# mael.net
KiCad netlist of a schematic drawn in EAGLE
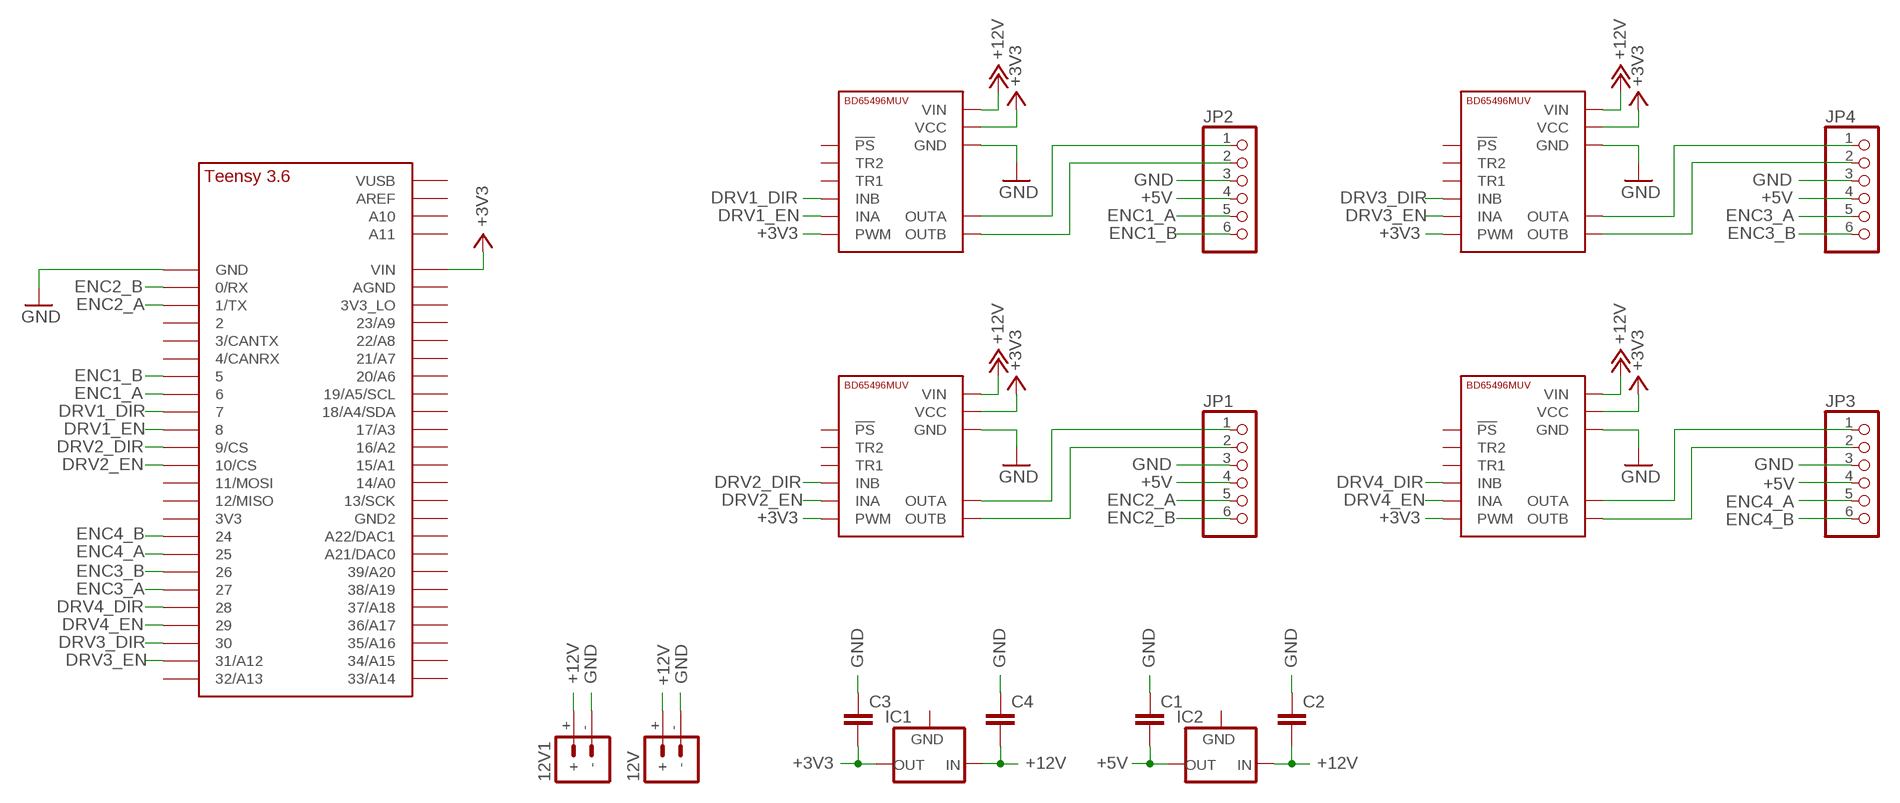
[diagram p0: schematic, sheet 1]

(export (version "E")
  (design (tool "Eeschema 10.0.6"))
  (components
    (comp (ref "12V")
      (value "BATTERY_CONN_DEANS")
      (footprint "eagle-import:DEANS")
      (libsource (lib "eagle-import") (part "BATTERY_CONN_DEANS"))
    )
    (comp (ref "12V1")
      (value "BATTERY_CONN_DEANS")
      (footprint "eagle-import:DEANS")
      (libsource (lib "eagle-import") (part "BATTERY_CONN_DEANS"))
    )
    (comp (ref "C1")
      (value "C-EU050-024X044")
      (footprint "eagle-import:C050-024X044")
      (libsource (lib "eagle-import") (part "C-EU050-024X044"))
    )
    (comp (ref "C2")
      (value "C-EU050-024X044")
      (footprint "eagle-import:C050-024X044")
      (libsource (lib "eagle-import") (part "C-EU050-024X044"))
    )
    (comp (ref "C3")
      (value "C-EU050-024X044")
      (footprint "eagle-import:C050-024X044")
      (libsource (lib "eagle-import") (part "C-EU050-024X044"))
    )
    (comp (ref "C4")
      (value "C-EU050-024X044")
      (footprint "eagle-import:C050-024X044")
      (libsource (lib "eagle-import") (part "C-EU050-024X044"))
    )
    (comp (ref "IC1")
      (value "78XXL")
      (footprint "eagle-import:78XXL")
      (libsource (lib "eagle-import") (part "78XXL"))
    )
    (comp (ref "IC2")
      (value "78XXL")
      (footprint "eagle-import:78XXL")
      (libsource (lib "eagle-import") (part "78XXL"))
    )
    (comp (ref "JP1")
      (value "PINHD-1X6")
      (footprint "eagle-import:1X06")
      (libsource (lib "eagle-import") (part "PINHD-1X6"))
    )
    (comp (ref "JP2")
      (value "PINHD-1X6")
      (footprint "eagle-import:1X06")
      (libsource (lib "eagle-import") (part "PINHD-1X6"))
    )
    (comp (ref "JP3")
      (value "PINHD-1X6")
      (footprint "eagle-import:1X06")
      (libsource (lib "eagle-import") (part "PINHD-1X6"))
    )
    (comp (ref "JP4")
      (value "PINHD-1X6")
      (footprint "eagle-import:1X06")
      (libsource (lib "eagle-import") (part "PINHD-1X6"))
    )
    (comp (ref "U$1")
      (value "BD65496MUV")
      (footprint "eagle-import:BD65496MUV")
      (libsource (lib "eagle-import") (part "BD65496MUV"))
    )
    (comp (ref "U$2")
      (value "TEENSY_3.5/3.6_BASIC")
      (footprint "eagle-import:TEENSY_3.5_3.6_BASIC")
      (libsource (lib "eagle-import") (part "TEENSY_3.5/3.6_BASIC"))
    )
    (comp (ref "U$3")
      (value "BD65496MUV")
      (footprint "eagle-import:BD65496MUV")
      (libsource (lib "eagle-import") (part "BD65496MUV"))
    )
    (comp (ref "U$4")
      (value "BD65496MUV")
      (footprint "eagle-import:BD65496MUV")
      (libsource (lib "eagle-import") (part "BD65496MUV"))
    )
    (comp (ref "U$5")
      (value "BD65496MUV")
      (footprint "eagle-import:BD65496MUV")
      (libsource (lib "eagle-import") (part "BD65496MUV"))
    )
  )
  (nets
    (net (code "1") (name "+3V3") (class "Default")
      (node (ref "C3") (pin "2") (pinfunction "2_2") (pintype "passive"))
      (node (ref "IC1") (pin "OUT") (pinfunction "OUT_OUT") (pintype "passive"))
      (node (ref "U$1") (pin "PWM") (pinfunction "PWM_PWM") (pintype "bidirectional"))
      (node (ref "U$1") (pin "VCC") (pinfunction "VCC_VCC") (pintype "bidirectional"))
      (node (ref "U$2") (pin "VIN") (pinfunction "VIN_VIN") (pintype "bidirectional"))
      (node (ref "U$3") (pin "PWM") (pinfunction "PWM_PWM") (pintype "bidirectional"))
      (node (ref "U$3") (pin "VCC") (pinfunction "VCC_VCC") (pintype "bidirectional"))
      (node (ref "U$4") (pin "PWM") (pinfunction "PWM_PWM") (pintype "bidirectional"))
      (node (ref "U$4") (pin "VCC") (pinfunction "VCC_VCC") (pintype "bidirectional"))
      (node (ref "U$5") (pin "PWM") (pinfunction "PWM_PWM") (pintype "bidirectional"))
      (node (ref "U$5") (pin "VCC") (pinfunction "VCC_VCC") (pintype "bidirectional"))
    )
    (net (code "2") (name "+12V") (class "Default")
      (node (ref "12V") (pin "+") (pinfunction "+_+") (pintype "passive"))
      (node (ref "12V1") (pin "+") (pinfunction "+_+") (pintype "passive"))
      (node (ref "C2") (pin "2") (pinfunction "2_2") (pintype "passive"))
      (node (ref "C4") (pin "2") (pinfunction "2_2") (pintype "passive"))
      (node (ref "IC1") (pin "IN") (pinfunction "IN_IN") (pintype "input"))
      (node (ref "IC2") (pin "IN") (pinfunction "IN_IN") (pintype "input"))
      (node (ref "U$1") (pin "VIN") (pinfunction "VIN_VIN") (pintype "bidirectional"))
      (node (ref "U$3") (pin "VIN") (pinfunction "VIN_VIN") (pintype "bidirectional"))
      (node (ref "U$4") (pin "VIN") (pinfunction "VIN_VIN") (pintype "bidirectional"))
      (node (ref "U$5") (pin "VIN") (pinfunction "VIN_VIN") (pintype "bidirectional"))
    )
    (net (code "3") (name "/+5V") (class "Default")
      (node (ref "C1") (pin "2") (pinfunction "2_2") (pintype "passive"))
      (node (ref "IC2") (pin "OUT") (pinfunction "OUT_OUT") (pintype "passive"))
      (node (ref "JP1") (pin "4") (pinfunction "4_4") (pintype "passive"))
      (node (ref "JP2") (pin "4") (pinfunction "4_4") (pintype "passive"))
      (node (ref "JP3") (pin "4") (pinfunction "4_4") (pintype "passive"))
      (node (ref "JP4") (pin "4") (pinfunction "4_4") (pintype "passive"))
    )
    (net (code "4") (name "/DRV1_DIR") (class "Default")
      (node (ref "U$1") (pin "INB") (pinfunction "INB_INB") (pintype "bidirectional"))
      (node (ref "U$2") (pin "7") (pinfunction "7_7") (pintype "bidirectional"))
    )
    (net (code "5") (name "/DRV1_EN") (class "Default")
      (node (ref "U$1") (pin "INA") (pinfunction "INA_INA") (pintype "bidirectional"))
      (node (ref "U$2") (pin "8") (pinfunction "8_8") (pintype "bidirectional"))
    )
    (net (code "6") (name "/DRV2_DIR") (class "Default")
      (node (ref "U$2") (pin "9/CS") (pinfunction "9/CS_9/CS") (pintype "bidirectional"))
      (node (ref "U$3") (pin "INB") (pinfunction "INB_INB") (pintype "bidirectional"))
    )
    (net (code "7") (name "/DRV2_EN") (class "Default")
      (node (ref "U$2") (pin "10/CS") (pinfunction "10/CS_10/CS") (pintype "bidirectional"))
      (node (ref "U$3") (pin "INA") (pinfunction "INA_INA") (pintype "bidirectional"))
    )
    (net (code "8") (name "/DRV3_DIR") (class "Default")
      (node (ref "U$2") (pin "30") (pinfunction "30_30") (pintype "bidirectional"))
      (node (ref "U$4") (pin "INB") (pinfunction "INB_INB") (pintype "bidirectional"))
    )
    (net (code "9") (name "/DRV3_EN") (class "Default")
      (node (ref "U$2") (pin "31/A12") (pinfunction "31/A12_31/A12") (pintype "bidirectional"))
      (node (ref "U$4") (pin "INA") (pinfunction "INA_INA") (pintype "bidirectional"))
    )
    (net (code "10") (name "/DRV4_DIR") (class "Default")
      (node (ref "U$2") (pin "28") (pinfunction "28_28") (pintype "bidirectional"))
      (node (ref "U$5") (pin "INB") (pinfunction "INB_INB") (pintype "bidirectional"))
    )
    (net (code "11") (name "/DRV4_EN") (class "Default")
      (node (ref "U$2") (pin "29") (pinfunction "29_29") (pintype "bidirectional"))
      (node (ref "U$5") (pin "INA") (pinfunction "INA_INA") (pintype "bidirectional"))
    )
    (net (code "12") (name "/ENC1_A") (class "Default")
      (node (ref "JP2") (pin "5") (pinfunction "5_5") (pintype "passive"))
      (node (ref "U$2") (pin "6") (pinfunction "6_6") (pintype "bidirectional"))
    )
    (net (code "13") (name "/ENC1_B") (class "Default")
      (node (ref "JP2") (pin "6") (pinfunction "6_6") (pintype "passive"))
      (node (ref "U$2") (pin "5") (pinfunction "5_5") (pintype "bidirectional"))
    )
    (net (code "14") (name "/ENC2_A") (class "Default")
      (node (ref "JP1") (pin "5") (pinfunction "5_5") (pintype "passive"))
      (node (ref "U$2") (pin "1/TX") (pinfunction "1/TX_1/TX") (pintype "bidirectional"))
    )
    (net (code "15") (name "/ENC2_B") (class "Default")
      (node (ref "JP1") (pin "6") (pinfunction "6_6") (pintype "passive"))
      (node (ref "U$2") (pin "0/RX") (pinfunction "0/RX_0/RX") (pintype "bidirectional"))
    )
    (net (code "16") (name "/ENC3_A") (class "Default")
      (node (ref "JP4") (pin "5") (pinfunction "5_5") (pintype "passive"))
      (node (ref "U$2") (pin "27") (pinfunction "27_27") (pintype "bidirectional"))
    )
    (net (code "17") (name "/ENC3_B") (class "Default")
      (node (ref "JP4") (pin "6") (pinfunction "6_6") (pintype "passive"))
      (node (ref "U$2") (pin "26") (pinfunction "26_26") (pintype "bidirectional"))
    )
    (net (code "18") (name "/ENC4_A") (class "Default")
      (node (ref "JP3") (pin "5") (pinfunction "5_5") (pintype "passive"))
      (node (ref "U$2") (pin "25") (pinfunction "25_25") (pintype "bidirectional"))
    )
    (net (code "19") (name "/ENC4_B") (class "Default")
      (node (ref "JP3") (pin "6") (pinfunction "6_6") (pintype "passive"))
      (node (ref "U$2") (pin "24") (pinfunction "24_24") (pintype "bidirectional"))
    )
    (net (code "20") (name "GND") (class "Default")
      (node (ref "12V") (pin "-") (pinfunction "-_-") (pintype "passive"))
      (node (ref "12V1") (pin "-") (pinfunction "-_-") (pintype "passive"))
      (node (ref "C1") (pin "1") (pinfunction "1_1") (pintype "passive"))
      (node (ref "C2") (pin "1") (pinfunction "1_1") (pintype "passive"))
      (node (ref "C3") (pin "1") (pinfunction "1_1") (pintype "passive"))
      (node (ref "C4") (pin "1") (pinfunction "1_1") (pintype "passive"))
      (node (ref "JP1") (pin "3") (pinfunction "3_3") (pintype "passive"))
      (node (ref "JP2") (pin "3") (pinfunction "3_3") (pintype "passive"))
      (node (ref "JP3") (pin "3") (pinfunction "3_3") (pintype "passive"))
      (node (ref "JP4") (pin "3") (pinfunction "3_3") (pintype "passive"))
      (node (ref "U$1") (pin "GND1") (pinfunction "GND_GND1") (pintype "bidirectional"))
      (node (ref "U$1") (pin "GND2") (pinfunction "GND_GND2") (pintype "bidirectional"))
      (node (ref "U$2") (pin "GND") (pinfunction "GND_GND") (pintype "bidirectional"))
      (node (ref "U$3") (pin "GND1") (pinfunction "GND_GND1") (pintype "bidirectional"))
      (node (ref "U$3") (pin "GND2") (pinfunction "GND_GND2") (pintype "bidirectional"))
      (node (ref "U$4") (pin "GND1") (pinfunction "GND_GND1") (pintype "bidirectional"))
      (node (ref "U$4") (pin "GND2") (pinfunction "GND_GND2") (pintype "bidirectional"))
      (node (ref "U$5") (pin "GND1") (pinfunction "GND_GND1") (pintype "bidirectional"))
      (node (ref "U$5") (pin "GND2") (pinfunction "GND_GND2") (pintype "bidirectional"))
    )
    (net (code "21") (name "Net-(JP1-Pad1)") (class "Default")
      (node (ref "JP1") (pin "1") (pinfunction "1_1") (pintype "passive"))
      (node (ref "U$3") (pin "OUTA") (pinfunction "OUTA_OUTA") (pintype "bidirectional"))
    )
    (net (code "22") (name "Net-(JP1-Pad2)") (class "Default")
      (node (ref "JP1") (pin "2") (pinfunction "2_2") (pintype "passive"))
      (node (ref "U$3") (pin "OUTB") (pinfunction "OUTB_OUTB") (pintype "bidirectional"))
    )
    (net (code "23") (name "Net-(JP2-Pad1)") (class "Default")
      (node (ref "JP2") (pin "1") (pinfunction "1_1") (pintype "passive"))
      (node (ref "U$1") (pin "OUTA") (pinfunction "OUTA_OUTA") (pintype "bidirectional"))
    )
    (net (code "24") (name "Net-(JP2-Pad2)") (class "Default")
      (node (ref "JP2") (pin "2") (pinfunction "2_2") (pintype "passive"))
      (node (ref "U$1") (pin "OUTB") (pinfunction "OUTB_OUTB") (pintype "bidirectional"))
    )
    (net (code "25") (name "Net-(JP3-Pad1)") (class "Default")
      (node (ref "JP3") (pin "1") (pinfunction "1_1") (pintype "passive"))
      (node (ref "U$5") (pin "OUTA") (pinfunction "OUTA_OUTA") (pintype "bidirectional"))
    )
    (net (code "26") (name "Net-(JP3-Pad2)") (class "Default")
      (node (ref "JP3") (pin "2") (pinfunction "2_2") (pintype "passive"))
      (node (ref "U$5") (pin "OUTB") (pinfunction "OUTB_OUTB") (pintype "bidirectional"))
    )
    (net (code "27") (name "Net-(JP4-Pad1)") (class "Default")
      (node (ref "JP4") (pin "1") (pinfunction "1_1") (pintype "passive"))
      (node (ref "U$4") (pin "OUTA") (pinfunction "OUTA_OUTA") (pintype "bidirectional"))
    )
    (net (code "28") (name "Net-(JP4-Pad2)") (class "Default")
      (node (ref "JP4") (pin "2") (pinfunction "2_2") (pintype "passive"))
      (node (ref "U$4") (pin "OUTB") (pinfunction "OUTB_OUTB") (pintype "bidirectional"))
    )
    (net (code "29") (name "unconnected-(IC1-PadGND)") (class "Default")
      (node (ref "IC1") (pin "GND") (pinfunction "GND_GND") (pintype "input"))
    )
    (net (code "30") (name "unconnected-(IC2-PadGND)") (class "Default")
      (node (ref "IC2") (pin "GND") (pinfunction "GND_GND") (pintype "input"))
    )
    (net (code "31") (name "unconnected-(U$1-PadTR1)") (class "Default")
      (node (ref "U$1") (pin "TR1") (pinfunction "TR1_TR1") (pintype "bidirectional"))
    )
    (net (code "32") (name "unconnected-(U$1-PadTR2)") (class "Default")
      (node (ref "U$1") (pin "TR2") (pinfunction "TR2_TR2") (pintype "bidirectional"))
    )
    (net (code "33") (name "unconnected-(U$1-~{PS}-Pad!PS)") (class "Default")
      (node (ref "U$1") (pin "!PS") (pinfunction "~{PS}_!PS") (pintype "bidirectional"))
    )
    (net (code "34") (name "unconnected-(U$2-A21{slash}DAC0-Pad21{slash}DAC0)") (class "Default")
      (node (ref "U$2") (pin "21/DAC0") (pinfunction "A21/DAC0_21/DAC0") (pintype "bidirectional"))
    )
    (net (code "35") (name "unconnected-(U$2-Pad2)") (class "Default")
      (node (ref "U$2") (pin "2") (pinfunction "2_2") (pintype "bidirectional"))
    )
    (net (code "36") (name "unconnected-(U$2-Pad3V3)") (class "Default")
      (node (ref "U$2") (pin "3V3") (pinfunction "3V3_3V3") (pintype "bidirectional"))
    )
    (net (code "37") (name "unconnected-(U$2-Pad3V3_LO)") (class "Default")
      (node (ref "U$2") (pin "3V3_LO") (pinfunction "3V3_LO_3V3_LO") (pintype "bidirectional"))
    )
    (net (code "38") (name "unconnected-(U$2-Pad3{slash}CANTX)") (class "Default")
      (node (ref "U$2") (pin "3/CANTX") (pinfunction "3/CANTX_3/CANTX") (pintype "bidirectional"))
    )
    (net (code "39") (name "unconnected-(U$2-Pad4{slash}CANRX)") (class "Default")
      (node (ref "U$2") (pin "4/CANRX") (pinfunction "4/CANRX_4/CANRX") (pintype "bidirectional"))
    )
    (net (code "40") (name "unconnected-(U$2-Pad11{slash}MOSI)") (class "Default")
      (node (ref "U$2") (pin "11/MOSI") (pinfunction "11/MOSI_11/MOSI") (pintype "bidirectional"))
    )
    (net (code "41") (name "unconnected-(U$2-Pad12{slash}MISO)") (class "Default")
      (node (ref "U$2") (pin "12/MISO") (pinfunction "12/MISO_12/MISO") (pintype "bidirectional"))
    )
    (net (code "42") (name "unconnected-(U$2-Pad13{slash}SCK)") (class "Default")
      (node (ref "U$2") (pin "13/SCK") (pinfunction "13/SCK_13/SCK") (pintype "bidirectional"))
    )
    (net (code "43") (name "unconnected-(U$2-Pad14{slash}A0)") (class "Default")
      (node (ref "U$2") (pin "14/A0") (pinfunction "14/A0_14/A0") (pintype "bidirectional"))
    )
    (net (code "44") (name "unconnected-(U$2-Pad15{slash}A1)") (class "Default")
      (node (ref "U$2") (pin "15/A1") (pinfunction "15/A1_15/A1") (pintype "bidirectional"))
    )
    (net (code "45") (name "unconnected-(U$2-Pad16{slash}A2)") (class "Default")
      (node (ref "U$2") (pin "16/A2") (pinfunction "16/A2_16/A2") (pintype "bidirectional"))
    )
    (net (code "46") (name "unconnected-(U$2-Pad17{slash}A3)") (class "Default")
      (node (ref "U$2") (pin "17/A3") (pinfunction "17/A3_17/A3") (pintype "bidirectional"))
    )
    (net (code "47") (name "unconnected-(U$2-Pad18{slash}A4{slash}SDA)") (class "Default")
      (node (ref "U$2") (pin "18/A4/SDA") (pinfunction "18/A4/SDA_18/A4/SDA") (pintype "bidirectional"))
    )
    (net (code "48") (name "unconnected-(U$2-Pad19{slash}A5{slash}SCL)") (class "Default")
      (node (ref "U$2") (pin "19/A5/SCL") (pinfunction "19/A5/SCL_19/A5/SCL") (pintype "bidirectional"))
    )
    (net (code "49") (name "unconnected-(U$2-Pad20{slash}A6)") (class "Default")
      (node (ref "U$2") (pin "20/A6") (pinfunction "20/A6_20/A6") (pintype "bidirectional"))
    )
    (net (code "50") (name "unconnected-(U$2-Pad21{slash}A7)") (class "Default")
      (node (ref "U$2") (pin "21/A7") (pinfunction "21/A7_21/A7") (pintype "bidirectional"))
    )
    (net (code "51") (name "unconnected-(U$2-Pad22{slash}A8)") (class "Default")
      (node (ref "U$2") (pin "22/A8") (pinfunction "22/A8_22/A8") (pintype "bidirectional"))
    )
    (net (code "52") (name "unconnected-(U$2-Pad23{slash}A9)") (class "Default")
      (node (ref "U$2") (pin "23/A9") (pinfunction "23/A9_23/A9") (pintype "bidirectional"))
    )
    (net (code "53") (name "unconnected-(U$2-Pad32{slash}A13)") (class "Default")
      (node (ref "U$2") (pin "32/A13") (pinfunction "32/A13_32/A13") (pintype "bidirectional"))
    )
    (net (code "54") (name "unconnected-(U$2-Pad33{slash}A14)") (class "Default")
      (node (ref "U$2") (pin "33/A14") (pinfunction "33/A14_33/A14") (pintype "bidirectional"))
    )
    (net (code "55") (name "unconnected-(U$2-Pad34{slash}A15)") (class "Default")
      (node (ref "U$2") (pin "34/A15") (pinfunction "34/A15_34/A15") (pintype "bidirectional"))
    )
    (net (code "56") (name "unconnected-(U$2-Pad35{slash}A16)") (class "Default")
      (node (ref "U$2") (pin "35/A16") (pinfunction "35/A16_35/A16") (pintype "bidirectional"))
    )
    (net (code "57") (name "unconnected-(U$2-Pad36{slash}A17)") (class "Default")
      (node (ref "U$2") (pin "36/A17") (pinfunction "36/A17_36/A17") (pintype "bidirectional"))
    )
    (net (code "58") (name "unconnected-(U$2-Pad37{slash}A18)") (class "Default")
      (node (ref "U$2") (pin "37/A18") (pinfunction "37/A18_37/A18") (pintype "bidirectional"))
    )
    (net (code "59") (name "unconnected-(U$2-Pad38{slash}A19)") (class "Default")
      (node (ref "U$2") (pin "38/A19") (pinfunction "38/A19_38/A19") (pintype "bidirectional"))
    )
    (net (code "60") (name "unconnected-(U$2-Pad39{slash}A20)") (class "Default")
      (node (ref "U$2") (pin "39/A20") (pinfunction "39/A20_39/A20") (pintype "bidirectional"))
    )
    (net (code "61") (name "unconnected-(U$2-PadA10)") (class "Default")
      (node (ref "U$2") (pin "A10") (pinfunction "A10_A10") (pintype "bidirectional"))
    )
    (net (code "62") (name "unconnected-(U$2-PadA11)") (class "Default")
      (node (ref "U$2") (pin "A11") (pinfunction "A11_A11") (pintype "bidirectional"))
    )
    (net (code "63") (name "unconnected-(U$2-PadA22{slash}DAC1)") (class "Default")
      (node (ref "U$2") (pin "A22/DAC1") (pinfunction "A22/DAC1_A22/DAC1") (pintype "bidirectional"))
    )
    (net (code "64") (name "unconnected-(U$2-PadAGND)") (class "Default")
      (node (ref "U$2") (pin "AGND") (pinfunction "AGND_AGND") (pintype "bidirectional"))
    )
    (net (code "65") (name "unconnected-(U$2-PadAREF)") (class "Default")
      (node (ref "U$2") (pin "AREF") (pinfunction "AREF_AREF") (pintype "bidirectional"))
    )
    (net (code "66") (name "unconnected-(U$2-PadGND2)") (class "Default")
      (node (ref "U$2") (pin "GND2") (pinfunction "GND2_GND2") (pintype "bidirectional"))
    )
    (net (code "67") (name "unconnected-(U$2-PadVUSB)") (class "Default")
      (node (ref "U$2") (pin "VUSB") (pinfunction "VUSB_VUSB") (pintype "bidirectional"))
    )
    (net (code "68") (name "unconnected-(U$3-PadTR1)") (class "Default")
      (node (ref "U$3") (pin "TR1") (pinfunction "TR1_TR1") (pintype "bidirectional"))
    )
    (net (code "69") (name "unconnected-(U$3-PadTR2)") (class "Default")
      (node (ref "U$3") (pin "TR2") (pinfunction "TR2_TR2") (pintype "bidirectional"))
    )
    (net (code "70") (name "unconnected-(U$3-~{PS}-Pad!PS)") (class "Default")
      (node (ref "U$3") (pin "!PS") (pinfunction "~{PS}_!PS") (pintype "bidirectional"))
    )
    (net (code "71") (name "unconnected-(U$4-PadTR1)") (class "Default")
      (node (ref "U$4") (pin "TR1") (pinfunction "TR1_TR1") (pintype "bidirectional"))
    )
    (net (code "72") (name "unconnected-(U$4-PadTR2)") (class "Default")
      (node (ref "U$4") (pin "TR2") (pinfunction "TR2_TR2") (pintype "bidirectional"))
    )
    (net (code "73") (name "unconnected-(U$4-~{PS}-Pad!PS)") (class "Default")
      (node (ref "U$4") (pin "!PS") (pinfunction "~{PS}_!PS") (pintype "bidirectional"))
    )
    (net (code "74") (name "unconnected-(U$5-PadTR1)") (class "Default")
      (node (ref "U$5") (pin "TR1") (pinfunction "TR1_TR1") (pintype "bidirectional"))
    )
    (net (code "75") (name "unconnected-(U$5-PadTR2)") (class "Default")
      (node (ref "U$5") (pin "TR2") (pinfunction "TR2_TR2") (pintype "bidirectional"))
    )
    (net (code "76") (name "unconnected-(U$5-~{PS}-Pad!PS)") (class "Default")
      (node (ref "U$5") (pin "!PS") (pinfunction "~{PS}_!PS") (pintype "bidirectional"))
    )
  )
)
